# node_vibration.net
KiCad netlist of a schematic drawn in EAGLE
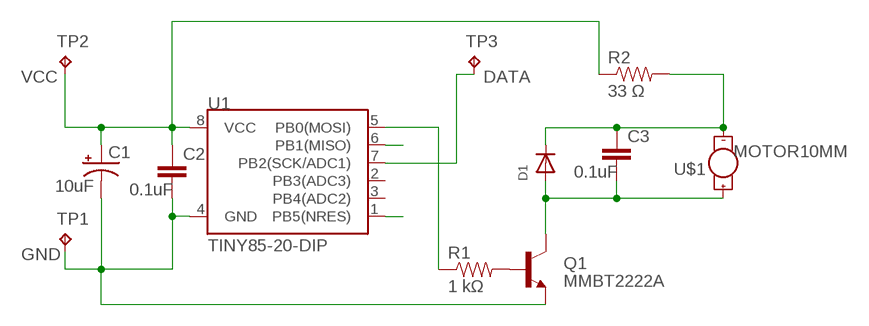
[diagram p0: schematic, sheet 1]

(export (version "E")
  (design (tool "Eeschema 10.0.6"))
  (components
    (comp (ref "C1")
      (value "10uF")
      (footprint "eagle-import:EIA3216")
      (libsource (lib "eagle-import") (part "10UF-16V-10%(TANT)"))
    )
    (comp (ref "C2")
      (value "0.1uF")
      (footprint "eagle-import:1206")
      (libsource (lib "eagle-import") (part "CAP1206"))
    )
    (comp (ref "C3")
      (value "0.1uF")
      (footprint "eagle-import:1206")
      (libsource (lib "eagle-import") (part "CAP1206"))
    )
    (comp (ref "D1")
      (value "DIODESMA")
      (footprint "eagle-import:SMADIODE")
      (libsource (lib "eagle-import") (part "DIODESMA"))
    )
    (comp (ref "Q1")
      (value "MMBT2222A")
      (footprint "eagle-import:SOT23-3")
      (libsource (lib "eagle-import") (part "TRANSISTOR_NPNMMBT2222A"))
    )
    (comp (ref "R1")
      (value "1 kΩ")
      (footprint "eagle-import:1206")
      (libsource (lib "eagle-import") (part "RESISTOR1206"))
    )
    (comp (ref "R2")
      (value "33 Ω")
      (footprint "eagle-import:1206")
      (libsource (lib "eagle-import") (part "RESISTOR1206"))
    )
    (comp (ref "TP1")
      (value "PADSTP13R")
      (footprint "eagle-import:CIRCLE-PAD-1_4")
      (fields (field (name "TP_SIGNAL_NAME") "GND"))
      (libsource (lib "eagle-import") (part "PADSTP13R"))
    )
    (comp (ref "TP2")
      (value "PADSTP13R")
      (footprint "eagle-import:CIRCLE-PAD-1_4")
      (fields (field (name "TP_SIGNAL_NAME") "VCC"))
      (libsource (lib "eagle-import") (part "PADSTP13R"))
    )
    (comp (ref "TP3")
      (value "PADSTP13R")
      (footprint "eagle-import:CIRCLE-PAD-1_4")
      (fields (field (name "TP_SIGNAL_NAME") "DATA"))
      (libsource (lib "eagle-import") (part "PADSTP13R"))
    )
    (comp (ref "U$1")
      (value "MOTOR10MM")
      (footprint "eagle-import:VIBE-MOTOR-10MM")
      (libsource (lib "eagle-import") (part "MOTOR10MM"))
    )
    (comp (ref "U1")
      (value "TINY85-20-DIP")
      (footprint "eagle-import:DIP08")
      (libsource (lib "eagle-import") (part "ATTINY45TINY45-20-DIP"))
    )
  )
  (nets
    (net (code "1") (name "Net-(C1-+)") (class "Default")
      (node (ref "C1") (pin "A") (pinfunction "+_A") (pintype "passive"))
      (node (ref "C2") (pin "1") (pinfunction "1_1") (pintype "passive"))
      (node (ref "R2") (pin "1") (pinfunction "1_1") (pintype "passive"))
      (node (ref "TP2") (pin "TP") (pinfunction "TP_TP") (pintype "input"))
      (node (ref "U1") (pin "8") (pinfunction "VCC_8") (pintype "bidirectional"))
    )
    (net (code "2") (name "Net-(C1--)") (class "Default")
      (node (ref "C1") (pin "C") (pinfunction "-_C") (pintype "passive"))
      (node (ref "C2") (pin "2") (pinfunction "2_2") (pintype "passive"))
      (node (ref "Q1") (pin "2") (pinfunction "E_2") (pintype "passive"))
      (node (ref "TP1") (pin "TP") (pinfunction "TP_TP") (pintype "input"))
      (node (ref "U1") (pin "4") (pinfunction "GND_4") (pintype "bidirectional"))
    )
    (net (code "3") (name "Net-(C3-Pad1)") (class "Default")
      (node (ref "C3") (pin "1") (pinfunction "1_1") (pintype "passive"))
      (node (ref "D1") (pin "C") (pinfunction "C_C") (pintype "passive"))
      (node (ref "R2") (pin "2") (pinfunction "2_2") (pintype "passive"))
      (node (ref "U$1") (pin "-") (pinfunction "-_-") (pintype "bidirectional"))
    )
    (net (code "4") (name "Net-(Q1-B)") (class "Default")
      (node (ref "Q1") (pin "1") (pinfunction "B_1") (pintype "passive"))
      (node (ref "R1") (pin "2") (pinfunction "2_2") (pintype "passive"))
    )
    (net (code "5") (name "Net-(Q1-C)") (class "Default")
      (node (ref "C3") (pin "2") (pinfunction "2_2") (pintype "passive"))
      (node (ref "D1") (pin "A") (pinfunction "A_A") (pintype "passive"))
      (node (ref "Q1") (pin "3") (pinfunction "C_3") (pintype "passive"))
      (node (ref "U$1") (pin "+") (pinfunction "+_+") (pintype "bidirectional"))
    )
    (net (code "6") (name "Net-(U1-PB0(MOSI))") (class "Default")
      (node (ref "R1") (pin "1") (pinfunction "1_1") (pintype "passive"))
      (node (ref "U1") (pin "5") (pinfunction "PB0(MOSI)_5") (pintype "bidirectional"))
    )
    (net (code "7") (name "Net-(U1-PB2(SCK{slash}ADC1))") (class "Default")
      (node (ref "TP3") (pin "TP") (pinfunction "TP_TP") (pintype "input"))
      (node (ref "U1") (pin "7") (pinfunction "PB2(SCK/ADC1)_7") (pintype "bidirectional"))
    )
    (net (code "8") (name "unconnected-(U1-PB1(MISO)-Pad6)") (class "Default")
      (node (ref "U1") (pin "6") (pinfunction "PB1(MISO)_6") (pintype "bidirectional"))
    )
    (net (code "9") (name "unconnected-(U1-PB3(ADC3)-Pad2)") (class "Default")
      (node (ref "U1") (pin "2") (pinfunction "PB3(ADC3)_2") (pintype "bidirectional"))
    )
    (net (code "10") (name "unconnected-(U1-PB4(ADC2)-Pad3)") (class "Default")
      (node (ref "U1") (pin "3") (pinfunction "PB4(ADC2)_3") (pintype "bidirectional"))
    )
    (net (code "11") (name "unconnected-(U1-PB5(NRES)-Pad1)") (class "Default")
      (node (ref "U1") (pin "1") (pinfunction "PB5(NRES)_1") (pintype "bidirectional"))
    )
  )
)
